# r9_1284.net
KiCad netlist of a schematic drawn in EAGLE
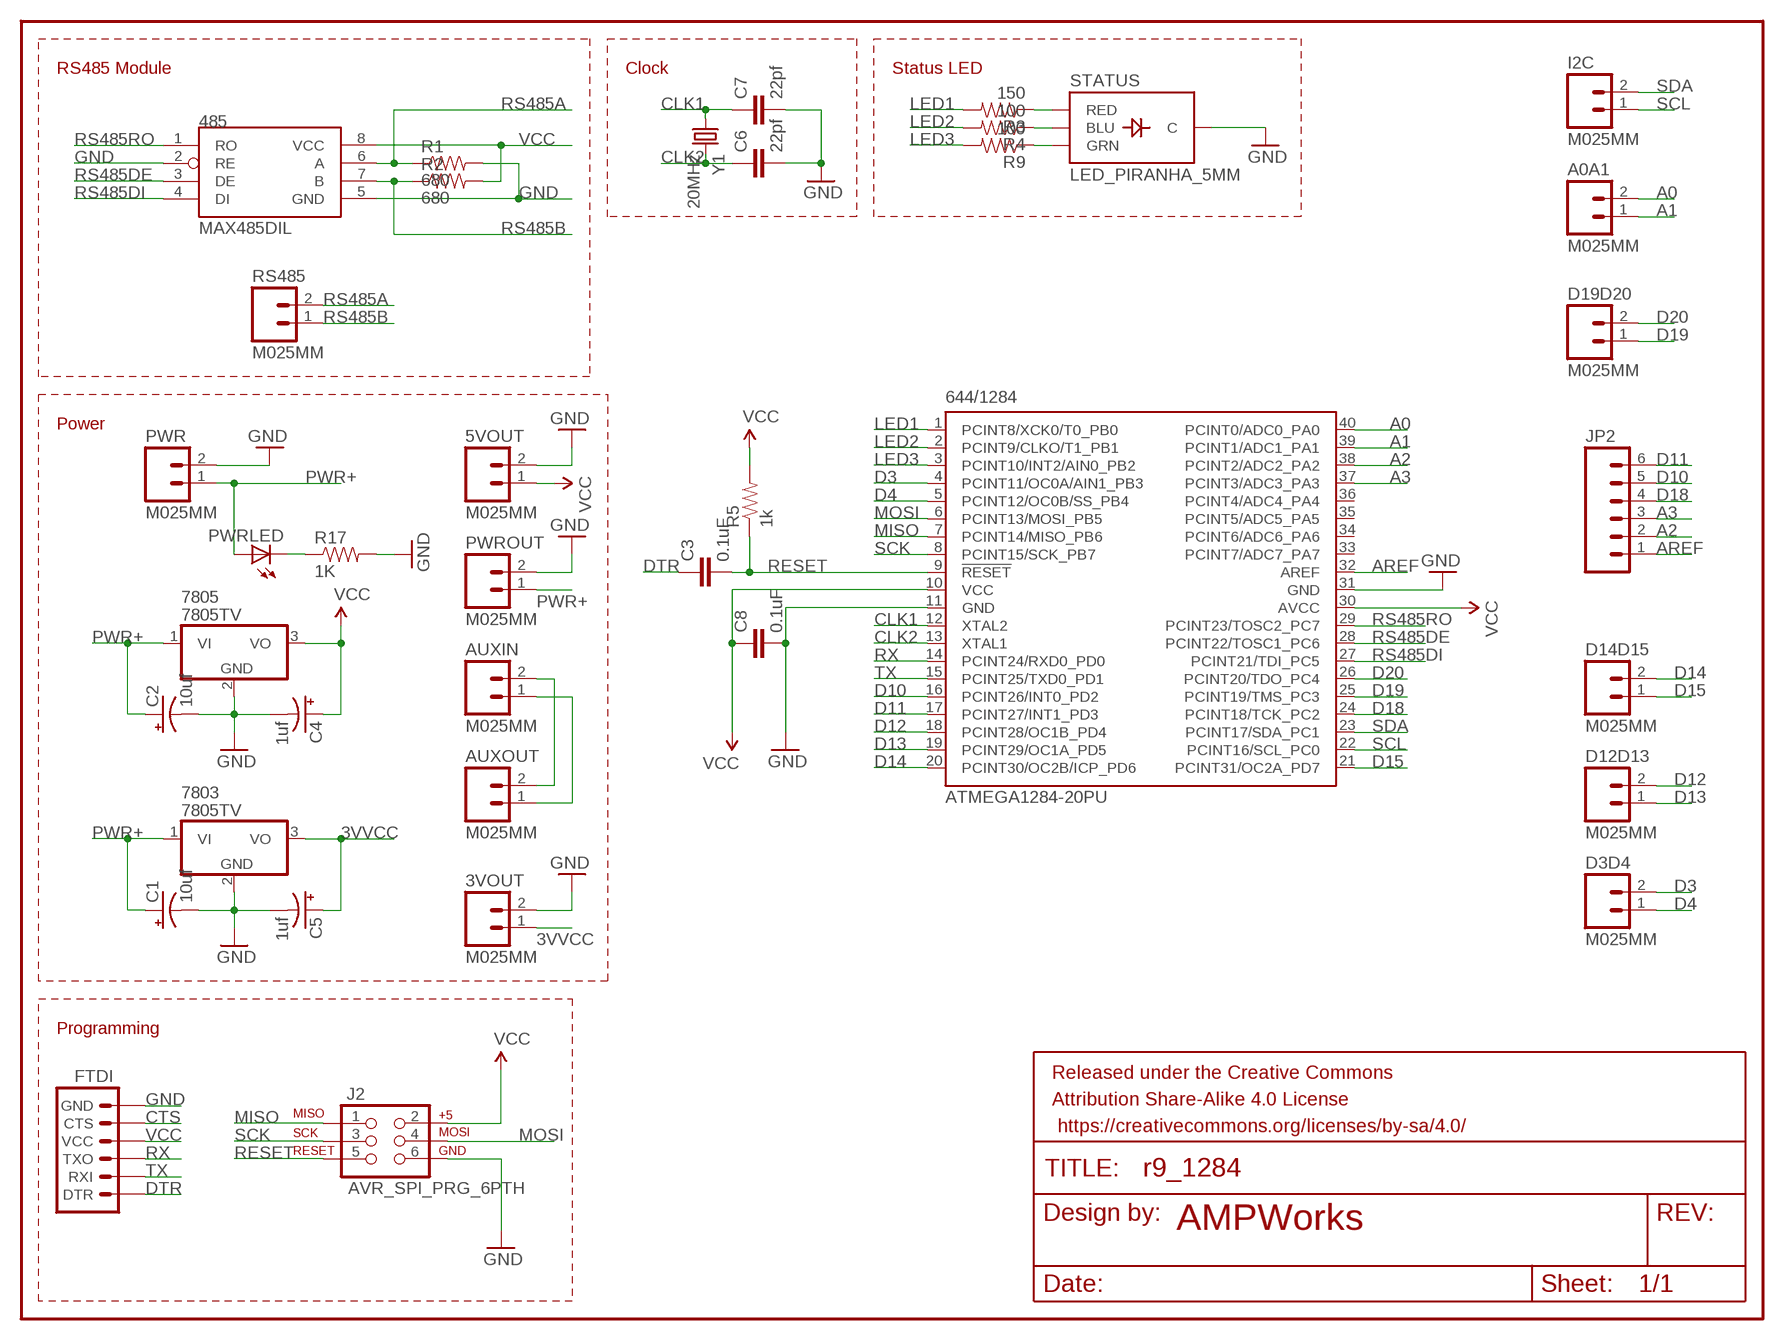
[diagram p0: schematic, sheet 1]

(export (version "E")
  (design (tool "Eeschema 10.0.6"))
  (components
    (comp (ref "3VOUT")
      (value "M025MM")
      (footprint "eagle-import:SCREWTERMINAL-5MM-2")
      (libsource (lib "eagle-import") (part "M025MM"))
    )
    (comp (ref "5VOUT")
      (value "M025MM")
      (footprint "eagle-import:SCREWTERMINAL-5MM-2")
      (libsource (lib "eagle-import") (part "M025MM"))
    )
    (comp (ref "485")
      (value "MAX485DIL")
      (footprint "eagle-import:DIL08")
      (libsource (lib "eagle-import") (part "MAX485DIL"))
    )
    (comp (ref "644/1284")
      (value "ATMEGA1284-20PU")
      (footprint "eagle-import:DIL40")
      (fields (field (name "MPN") "ATMEGA644-20PU"))
      (libsource (lib "eagle-import") (part "ATMEGA644-PU20"))
    )
    (comp (ref "7803")
      (value "7805TV")
      (footprint "eagle-import:TO220V")
      (libsource (lib "eagle-import") (part "78TV05"))
    )
    (comp (ref "7805")
      (value "7805TV")
      (footprint "eagle-import:TO220V")
      (libsource (lib "eagle-import") (part "78TV05"))
    )
    (comp (ref "A0A1")
      (value "M025MM")
      (footprint "eagle-import:SCREWTERMINAL-5MM-2")
      (libsource (lib "eagle-import") (part "M025MM"))
    )
    (comp (ref "AUXIN")
      (value "M025MM")
      (footprint "eagle-import:SCREWTERMINAL-5MM-2")
      (libsource (lib "eagle-import") (part "M025MM"))
    )
    (comp (ref "AUXOUT")
      (value "M025MM")
      (footprint "eagle-import:SCREWTERMINAL-5MM-2")
      (libsource (lib "eagle-import") (part "M025MM"))
    )
    (comp (ref "C1")
      (value "10uf")
      (footprint "eagle-import:CPOL-RADIAL-10UF-25V")
      (libsource (lib "eagle-import") (part "CAP_POLPTH2"))
    )
    (comp (ref "C2")
      (value "10uf")
      (footprint "eagle-import:CPOL-RADIAL-10UF-25V")
      (libsource (lib "eagle-import") (part "CAP_POLPTH2"))
    )
    (comp (ref "C3")
      (value "0.1uF")
      (footprint "eagle-import:CAP-PTH-SMALL")
      (libsource (lib "eagle-import") (part "CAPPTH"))
    )
    (comp (ref "C4")
      (value "1uf")
      (footprint "eagle-import:CPOL-RADIAL-10UF-25V")
      (libsource (lib "eagle-import") (part "CAP_POLPTH2"))
    )
    (comp (ref "C5")
      (value "1uf")
      (footprint "eagle-import:CPOL-RADIAL-10UF-25V")
      (libsource (lib "eagle-import") (part "CAP_POLPTH2"))
    )
    (comp (ref "C6")
      (value "22pf")
      (footprint "eagle-import:CAP-PTH-SMALL")
      (libsource (lib "eagle-import") (part "CAPPTH"))
    )
    (comp (ref "C7")
      (value "22pf")
      (footprint "eagle-import:CAP-PTH-SMALL")
      (libsource (lib "eagle-import") (part "CAPPTH"))
    )
    (comp (ref "C8")
      (value "0.1uF")
      (footprint "eagle-import:CAP-PTH-SMALL")
      (libsource (lib "eagle-import") (part "CAPPTH"))
    )
    (comp (ref "D3D4")
      (value "M025MM")
      (footprint "eagle-import:SCREWTERMINAL-5MM-2")
      (libsource (lib "eagle-import") (part "M025MM"))
    )
    (comp (ref "D12D13")
      (value "M025MM")
      (footprint "eagle-import:SCREWTERMINAL-5MM-2")
      (libsource (lib "eagle-import") (part "M025MM"))
    )
    (comp (ref "D14D15")
      (value "M025MM")
      (footprint "eagle-import:SCREWTERMINAL-5MM-2")
      (libsource (lib "eagle-import") (part "M025MM"))
    )
    (comp (ref "D19D20")
      (value "M025MM")
      (footprint "eagle-import:SCREWTERMINAL-5MM-2")
      (libsource (lib "eagle-import") (part "M025MM"))
    )
    (comp (ref "FRAME1")
      (value "FRAME-LETTER")
      (footprint "eagle-import:CREATIVE_COMMONS")
      (libsource (lib "eagle-import") (part "FRAME-LETTER"))
    )
    (comp (ref "FTDI")
      (value "ARDUINO_SERIAL_PROGRAMPTH")
      (footprint "eagle-import:1X06")
      (libsource (lib "eagle-import") (part "ARDUINO_SERIAL_PROGRAMPTH"))
    )
    (comp (ref "I2C")
      (value "M025MM")
      (footprint "eagle-import:SCREWTERMINAL-5MM-2")
      (libsource (lib "eagle-import") (part "M025MM"))
    )
    (comp (ref "J2")
      (value "AVR_SPI_PRG_6PTH")
      (footprint "eagle-import:2X3")
      (libsource (lib "eagle-import") (part "AVR_SPI_PRG_6PTH"))
    )
    (comp (ref "JP2")
      (value "M06NO_SILK")
      (footprint "eagle-import:1X06_NO_SILK")
      (libsource (lib "eagle-import") (part "M06NO_SILK"))
    )
    (comp (ref "PWR")
      (value "M025MM")
      (footprint "eagle-import:SCREWTERMINAL-5MM-2")
      (libsource (lib "eagle-import") (part "M025MM"))
    )
    (comp (ref "PWRLED")
      (value "LED5MM")
      (footprint "eagle-import:LED5MM")
      (libsource (lib "eagle-import") (part "LED5MM"))
    )
    (comp (ref "PWROUT")
      (value "M025MM")
      (footprint "eagle-import:SCREWTERMINAL-5MM-2")
      (libsource (lib "eagle-import") (part "M025MM"))
    )
    (comp (ref "R1")
      (value "680")
      (footprint "eagle-import:AXIAL-0.4")
      (libsource (lib "eagle-import") (part "SparkFun-Resistors_RESISTORPTH-1/4W"))
    )
    (comp (ref "R2")
      (value "680")
      (footprint "eagle-import:AXIAL-0.4")
      (libsource (lib "eagle-import") (part "SparkFun-Resistors_RESISTORPTH-1/4W"))
    )
    (comp (ref "R3")
      (value "150")
      (footprint "eagle-import:AXIAL-0.4")
      (libsource (lib "eagle-import") (part "RESISTORPTH-1/4W"))
    )
    (comp (ref "R4")
      (value "100")
      (footprint "eagle-import:AXIAL-0.4")
      (libsource (lib "eagle-import") (part "RESISTORPTH-1/4W"))
    )
    (comp (ref "R5")
      (value "1k")
      (footprint "eagle-import:AXIAL-0.4")
      (libsource (lib "eagle-import") (part "RESISTORPTH-1/4W"))
    )
    (comp (ref "R9")
      (value "100")
      (footprint "eagle-import:AXIAL-0.4")
      (libsource (lib "eagle-import") (part "RESISTORPTH-1/4W"))
    )
    (comp (ref "R17")
      (value "1K")
      (footprint "eagle-import:AXIAL-0.4")
      (libsource (lib "eagle-import") (part "SparkFun-Resistors_RESISTORPTH-1/4W"))
    )
    (comp (ref "RS485")
      (value "M025MM")
      (footprint "eagle-import:SCREWTERMINAL-5MM-2")
      (libsource (lib "eagle-import") (part "M025MM"))
    )
    (comp (ref "STATUS")
      (value "LED_PIRANHA_5MM")
      (footprint "eagle-import:LED_PIRANHA_5MM")
      (libsource (lib "eagle-import") (part "LED_PIRANHA_5MM"))
    )
    (comp (ref "Y1")
      (value "20MHz")
      (footprint "eagle-import:HC49US")
      (libsource (lib "eagle-import") (part "CRYSTALHC49US"))
    )
  )
  (nets
    (net (code "1") (name "/3VVCC") (class "Default")
      (node (ref "3VOUT") (pin "1") (pinfunction "1_1") (pintype "passive"))
      (node (ref "7803") (pin "3") (pinfunction "VO_3") (pintype "passive"))
      (node (ref "C5") (pin "1") (pinfunction "+_1") (pintype "passive"))
    )
    (net (code "2") (name "/A0") (class "Default")
      (node (ref "644/1284") (pin "40") (pinfunction "PCINT0/ADC0_PA0_40") (pintype "bidirectional"))
      (node (ref "A0A1") (pin "2") (pinfunction "2_2") (pintype "passive"))
    )
    (net (code "3") (name "/A1") (class "Default")
      (node (ref "644/1284") (pin "39") (pinfunction "PCINT1/ADC1_PA1_39") (pintype "bidirectional"))
      (node (ref "A0A1") (pin "1") (pinfunction "1_1") (pintype "passive"))
    )
    (net (code "4") (name "/A2") (class "Default")
      (node (ref "644/1284") (pin "38") (pinfunction "PCINT2/ADC2_PA2_38") (pintype "bidirectional"))
      (node (ref "JP2") (pin "2") (pinfunction "2_2") (pintype "passive"))
    )
    (net (code "5") (name "/A3") (class "Default")
      (node (ref "644/1284") (pin "37") (pinfunction "PCINT3/ADC3_PA3_37") (pintype "bidirectional"))
      (node (ref "JP2") (pin "3") (pinfunction "3_3") (pintype "passive"))
    )
    (net (code "6") (name "/AREF") (class "Default")
      (node (ref "644/1284") (pin "32") (pinfunction "AREF_32") (pintype "passive"))
      (node (ref "JP2") (pin "1") (pinfunction "1_1") (pintype "passive"))
    )
    (net (code "7") (name "/CLK1") (class "Default")
      (node (ref "644/1284") (pin "12") (pinfunction "XTAL2_12") (pintype "output"))
      (node (ref "C7") (pin "1") (pinfunction "1_1") (pintype "passive"))
      (node (ref "Y1") (pin "1") (pinfunction "1_1") (pintype "passive"))
    )
    (net (code "8") (name "/CLK2") (class "Default")
      (node (ref "644/1284") (pin "13") (pinfunction "XTAL1_13") (pintype "input"))
      (node (ref "C6") (pin "1") (pinfunction "1_1") (pintype "passive"))
      (node (ref "Y1") (pin "2") (pinfunction "2_2") (pintype "passive"))
    )
    (net (code "9") (name "/CTS") (class "Default")
      (node (ref "FTDI") (pin "CTS") (pinfunction "CTS_CTS") (pintype "passive"))
    )
    (net (code "10") (name "/D3") (class "Default")
      (node (ref "644/1284") (pin "4") (pinfunction "PCINT11/OC0A/AIN1_PB3_4") (pintype "bidirectional"))
      (node (ref "D3D4") (pin "2") (pinfunction "2_2") (pintype "passive"))
    )
    (net (code "11") (name "/D4") (class "Default")
      (node (ref "644/1284") (pin "5") (pinfunction "PCINT12/OC0B/SS_PB4_5") (pintype "bidirectional"))
      (node (ref "D3D4") (pin "1") (pinfunction "1_1") (pintype "passive"))
    )
    (net (code "12") (name "/D10") (class "Default")
      (node (ref "644/1284") (pin "16") (pinfunction "PCINT26/INT0_PD2_16") (pintype "bidirectional"))
      (node (ref "JP2") (pin "5") (pinfunction "5_5") (pintype "passive"))
    )
    (net (code "13") (name "/D11") (class "Default")
      (node (ref "644/1284") (pin "17") (pinfunction "PCINT27/INT1_PD3_17") (pintype "bidirectional"))
      (node (ref "JP2") (pin "6") (pinfunction "6_6") (pintype "passive"))
    )
    (net (code "14") (name "/D12") (class "Default")
      (node (ref "644/1284") (pin "18") (pinfunction "PCINT28/OC1B_PD4_18") (pintype "bidirectional"))
      (node (ref "D12D13") (pin "2") (pinfunction "2_2") (pintype "passive"))
    )
    (net (code "15") (name "/D13") (class "Default")
      (node (ref "644/1284") (pin "19") (pinfunction "PCINT29/OC1A_PD5_19") (pintype "bidirectional"))
      (node (ref "D12D13") (pin "1") (pinfunction "1_1") (pintype "passive"))
    )
    (net (code "16") (name "/D14") (class "Default")
      (node (ref "644/1284") (pin "20") (pinfunction "PCINT30/OC2B/ICP_PD6_20") (pintype "bidirectional"))
      (node (ref "D14D15") (pin "2") (pinfunction "2_2") (pintype "passive"))
    )
    (net (code "17") (name "/D15") (class "Default")
      (node (ref "644/1284") (pin "21") (pinfunction "PCINT31/OC2A_PD7_21") (pintype "bidirectional"))
      (node (ref "D14D15") (pin "1") (pinfunction "1_1") (pintype "passive"))
    )
    (net (code "18") (name "/D18") (class "Default")
      (node (ref "644/1284") (pin "24") (pinfunction "PCINT18/TCK_PC2_24") (pintype "bidirectional"))
      (node (ref "JP2") (pin "4") (pinfunction "4_4") (pintype "passive"))
    )
    (net (code "19") (name "/D19") (class "Default")
      (node (ref "644/1284") (pin "25") (pinfunction "PCINT19/TMS_PC3_25") (pintype "bidirectional"))
      (node (ref "D19D20") (pin "1") (pinfunction "1_1") (pintype "passive"))
    )
    (net (code "20") (name "/D20") (class "Default")
      (node (ref "644/1284") (pin "26") (pinfunction "PCINT20/TDO_PC4_26") (pintype "bidirectional"))
      (node (ref "D19D20") (pin "2") (pinfunction "2_2") (pintype "passive"))
    )
    (net (code "21") (name "/DTR") (class "Default")
      (node (ref "C3") (pin "1") (pinfunction "1_1") (pintype "passive"))
      (node (ref "FTDI") (pin "DTR") (pinfunction "DTR_DTR") (pintype "passive"))
    )
    (net (code "22") (name "/LED1") (class "Default")
      (node (ref "644/1284") (pin "1") (pinfunction "PCINT8/XCK0/T0_PB0_1") (pintype "bidirectional"))
      (node (ref "R3") (pin "P$2") (pinfunction "2_P$2") (pintype "passive"))
    )
    (net (code "23") (name "/LED2") (class "Default")
      (node (ref "644/1284") (pin "2") (pinfunction "PCINT9/CLKO/T1_PB1_2") (pintype "bidirectional"))
      (node (ref "R4") (pin "P$2") (pinfunction "2_P$2") (pintype "passive"))
    )
    (net (code "24") (name "/LED3") (class "Default")
      (node (ref "644/1284") (pin "3") (pinfunction "PCINT10/INT2/AIN0_PB2_3") (pintype "bidirectional"))
      (node (ref "R9") (pin "P$2") (pinfunction "2_P$2") (pintype "passive"))
    )
    (net (code "25") (name "/MISO") (class "Default")
      (node (ref "644/1284") (pin "7") (pinfunction "PCINT14/MISO_PB6_7") (pintype "bidirectional"))
      (node (ref "J2") (pin "1") (pinfunction "1_1") (pintype "passive"))
    )
    (net (code "26") (name "/MOSI") (class "Default")
      (node (ref "644/1284") (pin "6") (pinfunction "PCINT13/MOSI_PB5_6") (pintype "bidirectional"))
      (node (ref "J2") (pin "4") (pinfunction "4_4") (pintype "passive"))
    )
    (net (code "27") (name "/PWR+") (class "Default")
      (node (ref "7803") (pin "1") (pinfunction "VI_1") (pintype "input"))
      (node (ref "7805") (pin "1") (pinfunction "VI_1") (pintype "input"))
      (node (ref "C1") (pin "1") (pinfunction "+_1") (pintype "passive"))
      (node (ref "C2") (pin "1") (pinfunction "+_1") (pintype "passive"))
      (node (ref "PWR") (pin "1") (pinfunction "1_1") (pintype "passive"))
      (node (ref "PWRLED") (pin "A") (pinfunction "A_A") (pintype "passive"))
      (node (ref "PWROUT") (pin "1") (pinfunction "1_1") (pintype "passive"))
    )
    (net (code "28") (name "/RESET") (class "Default")
      (node (ref "644/1284") (pin "9") (pinfunction "~{RESET}_9") (pintype "input"))
      (node (ref "C3") (pin "2") (pinfunction "2_2") (pintype "passive"))
      (node (ref "J2") (pin "5") (pinfunction "5_5") (pintype "passive"))
      (node (ref "R5") (pin "P$1") (pinfunction "1_P$1") (pintype "passive"))
    )
    (net (code "29") (name "/RS485A") (class "Default")
      (node (ref "485") (pin "6") (pinfunction "A_6") (pintype "bidirectional"))
      (node (ref "R1") (pin "P$1") (pinfunction "1_P$1") (pintype "passive"))
      (node (ref "RS485") (pin "2") (pinfunction "2_2") (pintype "passive"))
    )
    (net (code "30") (name "/RS485B") (class "Default")
      (node (ref "485") (pin "7") (pinfunction "B_7") (pintype "bidirectional"))
      (node (ref "R2") (pin "P$1") (pinfunction "1_P$1") (pintype "passive"))
      (node (ref "RS485") (pin "1") (pinfunction "1_1") (pintype "passive"))
    )
    (net (code "31") (name "/RS485DE") (class "Default")
      (node (ref "485") (pin "3") (pinfunction "DE_3") (pintype "bidirectional"))
      (node (ref "644/1284") (pin "28") (pinfunction "PCINT22/TOSC1_PC6_28") (pintype "bidirectional"))
    )
    (net (code "32") (name "/RS485DI") (class "Default")
      (node (ref "485") (pin "4") (pinfunction "DI_4") (pintype "bidirectional"))
      (node (ref "644/1284") (pin "27") (pinfunction "PCINT21/TDI_PC5_27") (pintype "bidirectional"))
    )
    (net (code "33") (name "/RS485RO") (class "Default")
      (node (ref "485") (pin "1") (pinfunction "RO_1") (pintype "bidirectional"))
      (node (ref "644/1284") (pin "29") (pinfunction "PCINT23/TOSC2_PC7_29") (pintype "bidirectional"))
    )
    (net (code "34") (name "/RX") (class "Default")
      (node (ref "644/1284") (pin "14") (pinfunction "PCINT24/RXD0_PD0_14") (pintype "bidirectional"))
      (node (ref "FTDI") (pin "TXO") (pinfunction "TXO_TXO") (pintype "passive"))
    )
    (net (code "35") (name "/SCK") (class "Default")
      (node (ref "644/1284") (pin "8") (pinfunction "PCINT15/SCK_PB7_8") (pintype "bidirectional"))
      (node (ref "J2") (pin "3") (pinfunction "3_3") (pintype "passive"))
    )
    (net (code "36") (name "/SCL") (class "Default")
      (node (ref "644/1284") (pin "22") (pinfunction "PCINT16/SCL_PC0_22") (pintype "bidirectional"))
      (node (ref "I2C") (pin "1") (pinfunction "1_1") (pintype "passive"))
    )
    (net (code "37") (name "/SDA") (class "Default")
      (node (ref "644/1284") (pin "23") (pinfunction "PCINT17/SDA_PC1_23") (pintype "bidirectional"))
      (node (ref "I2C") (pin "2") (pinfunction "2_2") (pintype "passive"))
    )
    (net (code "38") (name "/TX") (class "Default")
      (node (ref "644/1284") (pin "15") (pinfunction "PCINT25/TXD0_PD1_15") (pintype "bidirectional"))
      (node (ref "FTDI") (pin "RXI") (pinfunction "RXI_RXI") (pintype "passive"))
    )
    (net (code "39") (name "GND") (class "Default")
      (node (ref "3VOUT") (pin "2") (pinfunction "2_2") (pintype "passive"))
      (node (ref "485") (pin "2") (pinfunction "RE_2") (pintype "bidirectional"))
      (node (ref "485") (pin "5") (pinfunction "GND_5") (pintype "bidirectional"))
      (node (ref "5VOUT") (pin "2") (pinfunction "2_2") (pintype "passive"))
      (node (ref "644/1284") (pin "11") (pinfunction "GND_11") (pintype "power_in"))
      (node (ref "644/1284") (pin "31") (pinfunction "GND_31") (pintype "power_in"))
      (node (ref "7803") (pin "2") (pinfunction "GND_2") (pintype "passive"))
      (node (ref "7805") (pin "2") (pinfunction "GND_2") (pintype "passive"))
      (node (ref "C1") (pin "2") (pinfunction "-_2") (pintype "passive"))
      (node (ref "C2") (pin "2") (pinfunction "-_2") (pintype "passive"))
      (node (ref "C4") (pin "2") (pinfunction "-_2") (pintype "passive"))
      (node (ref "C5") (pin "2") (pinfunction "-_2") (pintype "passive"))
      (node (ref "C6") (pin "2") (pinfunction "2_2") (pintype "passive"))
      (node (ref "C7") (pin "2") (pinfunction "2_2") (pintype "passive"))
      (node (ref "C8") (pin "2") (pinfunction "2_2") (pintype "passive"))
      (node (ref "FTDI") (pin "GND") (pinfunction "GND_GND") (pintype "passive"))
      (node (ref "J2") (pin "6") (pinfunction "6_6") (pintype "passive"))
      (node (ref "PWR") (pin "2") (pinfunction "2_2") (pintype "passive"))
      (node (ref "PWROUT") (pin "2") (pinfunction "2_2") (pintype "passive"))
      (node (ref "R1") (pin "P$2") (pinfunction "2_P$2") (pintype "passive"))
      (node (ref "R17") (pin "P$2") (pinfunction "2_P$2") (pintype "passive"))
      (node (ref "STATUS") (pin "-") (pinfunction "C_-") (pintype "bidirectional"))
    )
    (net (code "40") (name "Net-(AUXIN-Pad1)") (class "Default")
      (node (ref "AUXIN") (pin "1") (pinfunction "1_1") (pintype "passive"))
      (node (ref "AUXOUT") (pin "1") (pinfunction "1_1") (pintype "passive"))
    )
    (net (code "41") (name "Net-(AUXIN-Pad2)") (class "Default")
      (node (ref "AUXIN") (pin "2") (pinfunction "2_2") (pintype "passive"))
      (node (ref "AUXOUT") (pin "2") (pinfunction "2_2") (pintype "passive"))
    )
    (net (code "42") (name "Net-(PWRLED-C)") (class "Default")
      (node (ref "PWRLED") (pin "K") (pinfunction "C_K") (pintype "passive"))
      (node (ref "R17") (pin "P$1") (pinfunction "1_P$1") (pintype "passive"))
    )
    (net (code "43") (name "Net-(R3-1)") (class "Default")
      (node (ref "R3") (pin "P$1") (pinfunction "1_P$1") (pintype "passive"))
      (node (ref "STATUS") (pin "R") (pinfunction "RED_R") (pintype "bidirectional"))
    )
    (net (code "44") (name "Net-(R4-1)") (class "Default")
      (node (ref "R4") (pin "P$1") (pinfunction "1_P$1") (pintype "passive"))
      (node (ref "STATUS") (pin "B") (pinfunction "BLU_B") (pintype "bidirectional"))
    )
    (net (code "45") (name "Net-(R9-1)") (class "Default")
      (node (ref "R9") (pin "P$1") (pinfunction "1_P$1") (pintype "passive"))
      (node (ref "STATUS") (pin "G") (pinfunction "GRN_G") (pintype "bidirectional"))
    )
    (net (code "46") (name "VCC") (class "Default")
      (node (ref "485") (pin "8") (pinfunction "VCC_8") (pintype "bidirectional"))
      (node (ref "5VOUT") (pin "1") (pinfunction "1_1") (pintype "passive"))
      (node (ref "644/1284") (pin "10") (pinfunction "VCC_10") (pintype "power_in"))
      (node (ref "644/1284") (pin "30") (pinfunction "AVCC_30") (pintype "power_in"))
      (node (ref "7805") (pin "3") (pinfunction "VO_3") (pintype "passive"))
      (node (ref "C4") (pin "1") (pinfunction "+_1") (pintype "passive"))
      (node (ref "C8") (pin "1") (pinfunction "1_1") (pintype "passive"))
      (node (ref "FTDI") (pin "VCC") (pinfunction "VCC_VCC") (pintype "passive"))
      (node (ref "J2") (pin "2") (pinfunction "2_2") (pintype "passive"))
      (node (ref "R2") (pin "P$2") (pinfunction "2_P$2") (pintype "passive"))
      (node (ref "R5") (pin "P$2") (pinfunction "2_P$2") (pintype "passive"))
    )
    (net (code "47") (name "unconnected-(644/1284-PCINT4{slash}ADC4_PA4-Pad36)") (class "Default")
      (node (ref "644/1284") (pin "36") (pinfunction "PCINT4/ADC4_PA4_36") (pintype "bidirectional"))
    )
    (net (code "48") (name "unconnected-(644/1284-PCINT5{slash}ADC5_PA5-Pad35)") (class "Default")
      (node (ref "644/1284") (pin "35") (pinfunction "PCINT5/ADC5_PA5_35") (pintype "bidirectional"))
    )
    (net (code "49") (name "unconnected-(644/1284-PCINT6{slash}ADC6_PA6-Pad34)") (class "Default")
      (node (ref "644/1284") (pin "34") (pinfunction "PCINT6/ADC6_PA6_34") (pintype "bidirectional"))
    )
    (net (code "50") (name "unconnected-(644/1284-PCINT7{slash}ADC7_PA7-Pad33)") (class "Default")
      (node (ref "644/1284") (pin "33") (pinfunction "PCINT7/ADC7_PA7_33") (pintype "bidirectional"))
    )
  )
)
